# Parasite.net
KiCad netlist of a schematic drawn in Altium Designer
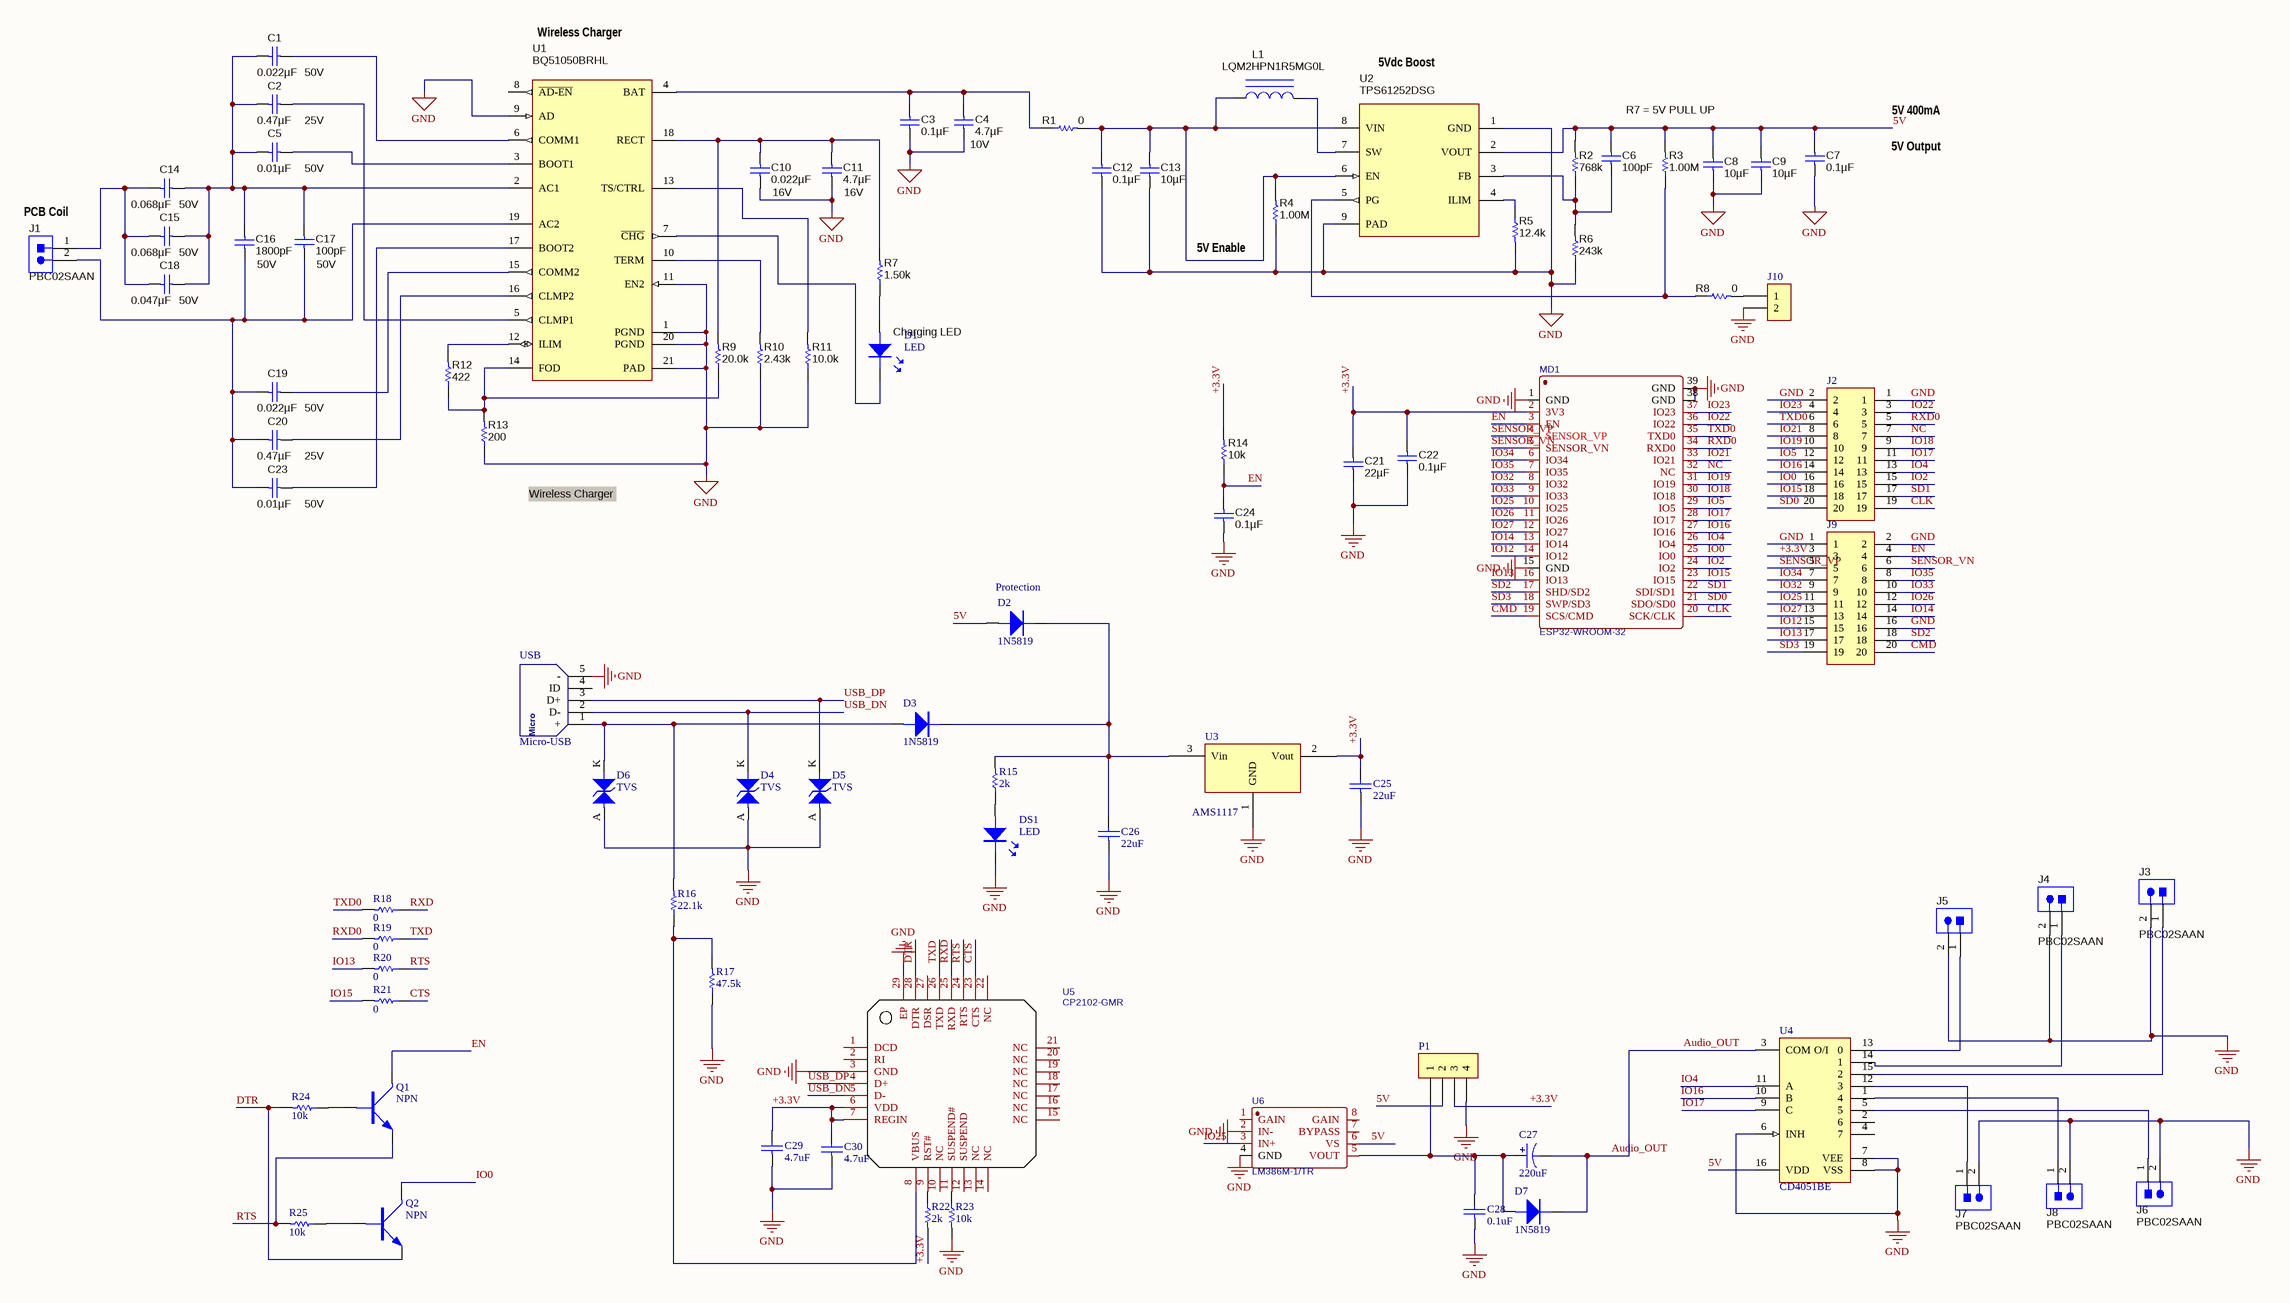
[diagram p0: Parasite.SchDoc]

(export (version "E")
  (design (tool "Eeschema 10.0.6"))
  (components
    (comp (ref "C1")
      (value "GRM155R71H223KA12D")
      (footprint "0603C")
      (description "CAP, CERM, 0.022 µF, 50 V, +/- 10%, X7R, 0402")
      (fields
        (field (name "VALUEDISPLAYED") "0.022µF")
        (field (name "MANUFACTURER") "MuRata")
        (field (name "VALUE2") "50V")
        (field (name "PUBLISHER") "Texas Instruments")
      )
      (libsource (lib "magsound") (part "GRM155R71H223KA12D"))
    )
    (comp (ref "C2")
      (value "~")
      (footprint "0603C")
      (description "CAP, CERM, 0.47 µF, 25 V, +/- 10%, X7R, 0603")
      (fields
        (field (name "PARTNUMBER") "GRM188R71E474KA12D")
        (field (name "VALUEDISPLAYED") "0.47µF")
        (field (name "MANUFACTURER") "MuRata")
        (field (name "VALUE2") "25V")
        (field (name "PUBLISHER") "Texas Instruments")
      )
      (libsource (lib "magsound") (part "GRM188R71E474KA12D"))
    )
    (comp (ref "C3")
      (value "GRM155R71A104KA01D")
      (footprint "0603C")
      (description "CAP, CERM, 0.1 µF, 10 V, +/- 10%, X7R, 0402")
      (fields
        (field (name "VALUEDISPLAYED") "0.1µF")
        (field (name "MANUFACTURER") "MuRata")
        (field (name "PUBLISHER") "Texas Instruments")
      )
      (libsource (lib "Capacitor_Ceramic") (part "GRM155R71A104KA01D"))
    )
    (comp (ref "C4")
      (value "C1005X5R1A475K050BC")
      (footprint "0603C")
      (description "CAP, CERM, 4.7 µF, 10 V, +/- 10%, X5R, 0402")
      (fields
        (field (name "VALUEDISPLAYED") "4.7µF")
        (field (name "MANUFACTURER") "TDK")
        (field (name "VALUE2") "10V")
        (field (name "PUBLISHER") "Texas Instruments")
      )
      (libsource (lib "Capacitor_Ceramic") (part "C1005X5R1A475K050BC"))
    )
    (comp (ref "C5")
      (value "~")
      (footprint "0603C")
      (description "CAP, CERM, 0.01 µF, 50 V, +/- 5%, X7R, 0402")
      (fields
        (field (name "PARTNUMBER") "C0402C103J5RACTU")
        (field (name "VALUEDISPLAYED") "0.01µF")
        (field (name "MANUFACTURER") "Kemet")
        (field (name "VALUE2") "50V")
        (field (name "PUBLISHER") "Texas Instruments")
      )
      (libsource (lib "magsound") (part "C0402C103J5RACTU"))
    )
    (comp (ref "C6")
      (value "CC0402JRNPO9BN101")
      (footprint "0603C")
      (description "CAP, CERM, 100 pF, 50 V, +/- 5%, C0G/NP0, 0402")
      (fields
        (field (name "VALUEDISPLAYED") "100pF")
        (field (name "MANUFACTURER") "Yageo America")
        (field (name "PUBLISHER") "Texas Instruments")
      )
      (libsource (lib "Capacitor_Ceramic") (part "CC0402JRNPO9BN101"))
    )
    (comp (ref "C7")
      (value "GRM155R71A104KA01D")
      (footprint "0603C")
      (description "CAP, CERM, 0.1 µF, 10 V, +/- 10%, X7R, 0402")
      (fields
        (field (name "VALUEDISPLAYED") "0.1µF")
        (field (name "MANUFACTURER") "MuRata")
        (field (name "PUBLISHER") "Texas Instruments")
      )
      (libsource (lib "Capacitor_Ceramic") (part "GRM155R71A104KA01D"))
    )
    (comp (ref "C8")
      (value "C0603C106M9PACTU")
      (footprint "0603C")
      (description "CAP, CERM, 10 µF, 6.3 V, +/- 20%, X5R, 0603")
      (fields
        (field (name "VALUEDISPLAYED") "10µF")
        (field (name "MANUFACTURER") "Kemet")
        (field (name "PUBLISHER") "Texas Instruments")
      )
      (libsource (lib "Capacitor_Ceramic") (part "C0603C106M9PACTU"))
    )
    (comp (ref "C9")
      (value "C0603C106M9PACTU")
      (footprint "0603C")
      (description "CAP, CERM, 10 µF, 6.3 V, +/- 20%, X5R, 0603")
      (fields
        (field (name "VALUEDISPLAYED") "10µF")
        (field (name "MANUFACTURER") "Kemet")
        (field (name "PUBLISHER") "Texas Instruments")
      )
      (libsource (lib "Capacitor_Ceramic") (part "C0603C106M9PACTU"))
    )
    (comp (ref "C10")
      (value "C1005X7R1C223K")
      (footprint "0603C")
      (description "CAP, CERM, 0.022 µF, 16 V, +/- 10%, X7R, 0402")
      (fields
        (field (name "VALUEDISPLAYED") "0.022µF")
        (field (name "MANUFACTURER") "TDK")
        (field (name "VALUE2") "16V")
        (field (name "PUBLISHER") "Texas Instruments")
      )
      (libsource (lib "Capacitor_Ceramic") (part "C1005X7R1C223K"))
    )
    (comp (ref "C11")
      (value "GRM188R61C475KAAJ")
      (footprint "0603C")
      (description "CAP, CERM, 4.7 µF, 16 V, +/- 10%, X5R, 0603")
      (fields
        (field (name "VALUEDISPLAYED") "4.7µF")
        (field (name "MANUFACTURER") "MuRata")
        (field (name "VALUE2") "16V")
        (field (name "PUBLISHER") "Texas Instruments")
      )
      (libsource (lib "Capacitor_Ceramic") (part "GRM188R61C475KAAJ"))
    )
    (comp (ref "C12")
      (value "GRM155R71A104KA01D")
      (footprint "0603C")
      (description "CAP, CERM, 0.1 µF, 10 V, +/- 10%, X7R, 0402")
      (fields
        (field (name "VALUEDISPLAYED") "0.1µF")
        (field (name "MANUFACTURER") "MuRata")
        (field (name "PUBLISHER") "Texas Instruments")
      )
      (libsource (lib "Capacitor_Ceramic") (part "GRM155R71A104KA01D"))
    )
    (comp (ref "C13")
      (value "C0603C106M9PACTU")
      (footprint "0603C")
      (description "CAP, CERM, 10 µF, 6.3 V, +/- 20%, X5R, 0603")
      (fields
        (field (name "VALUEDISPLAYED") "10µF")
        (field (name "MANUFACTURER") "Kemet")
        (field (name "PUBLISHER") "Texas Instruments")
      )
      (libsource (lib "Capacitor_Ceramic") (part "C0603C106M9PACTU"))
    )
    (comp (ref "C14")
      (value "C1005X7R1H683K")
      (footprint "0603C")
      (description "CAP, CERM, 0.068 µF, 50 V, +/- 10%, X7R, 0402")
      (fields
        (field (name "VALUEDISPLAYED") "0.068µF")
        (field (name "MANUFACTURER") "TDK")
        (field (name "VALUE2") "50V")
        (field (name "PUBLISHER") "Texas Instruments")
      )
      (libsource (lib "Capacitor_Ceramic") (part "C1005X7R1H683K"))
    )
    (comp (ref "C15")
      (value "C1005X7R1H683K")
      (footprint "0603C")
      (description "CAP, CERM, 0.068 µF, 50 V, +/- 10%, X7R, 0402")
      (fields
        (field (name "VALUEDISPLAYED") "0.068µF")
        (field (name "MANUFACTURER") "TDK")
        (field (name "VALUE2") "50V")
        (field (name "PUBLISHER") "Texas Instruments")
      )
      (libsource (lib "Capacitor_Ceramic") (part "C1005X7R1H683K"))
    )
    (comp (ref "C16")
      (value "GRM1885C1H182JA01D")
      (footprint "0603C")
      (description "CAP, CERM, 1800 pF, 50 V, +/- 5%, C0G/NP0, 0603")
      (fields
        (field (name "VALUEDISPLAYED") "1800pF")
        (field (name "MANUFACTURER") "MuRata")
        (field (name "VALUE2") "50V")
        (field (name "PUBLISHER") "Texas Instruments")
      )
      (libsource (lib "Capacitor_Ceramic") (part "GRM1885C1H182JA01D"))
    )
    (comp (ref "C17")
      (value "CC0402JRNPO9BN101")
      (footprint "0603C")
      (description "CAP, CERM, 100 pF, 50 V, +/- 5%, C0G/NP0, 0402")
      (fields
        (field (name "VALUEDISPLAYED") "100pF")
        (field (name "MANUFACTURER") "Yageo America")
        (field (name "VALUE2") "50V")
        (field (name "PUBLISHER") "Texas Instruments")
      )
      (libsource (lib "Capacitor_Ceramic") (part "CC0402JRNPO9BN101"))
    )
    (comp (ref "C18")
      (value "GRM188R71H473KA61D")
      (footprint "0603C")
      (description "CAP, CERM, 0.047 µF, 50 V, +/- 10%, X7R, 0603")
      (fields
        (field (name "VALUEDISPLAYED") "0.047µF")
        (field (name "MANUFACTURER") "MuRata")
        (field (name "VALUE2") "50V")
        (field (name "PUBLISHER") "Texas Instruments")
      )
      (libsource (lib "Capacitor_Ceramic") (part "GRM188R71H473KA61D"))
    )
    (comp (ref "C19")
      (value "GRM155R71H223KA12D")
      (footprint "0603C")
      (description "CAP, CERM, 0.022 µF, 50 V, +/- 10%, X7R, 0402")
      (fields
        (field (name "VALUEDISPLAYED") "0.022µF")
        (field (name "MANUFACTURER") "MuRata")
        (field (name "VALUE2") "50V")
        (field (name "PUBLISHER") "Texas Instruments")
      )
      (libsource (lib "Capacitor_Ceramic") (part "GRM155R71H223KA12D"))
    )
    (comp (ref "C20")
      (value "GRM188R71E474KA12D")
      (footprint "0603C")
      (description "CAP, CERM, 0.47 µF, 25 V, +/- 10%, X7R, 0603")
      (fields
        (field (name "VALUEDISPLAYED") "0.47µF")
        (field (name "MANUFACTURER") "MuRata")
        (field (name "VALUE2") "25V")
        (field (name "PUBLISHER") "Texas Instruments")
      )
      (libsource (lib "Capacitor_Ceramic") (part "GRM188R71E474KA12D"))
    )
    (comp (ref "C21")
      (value "GRM155R71A104KA01D")
      (footprint "0603C")
      (description "CAP, CERM, 0.1 µF, 10 V, +/- 10%, X7R, 0402")
      (fields
        (field (name "VALUEDISPLAYED") "22µF")
        (field (name "MANUFACTURER") "MuRata")
        (field (name "PUBLISHER") "Texas Instruments")
      )
      (libsource (lib "Capacitor_Ceramic") (part "GRM155R71A104KA01D"))
    )
    (comp (ref "C22")
      (value "GRM155R71A104KA01D")
      (footprint "0603C")
      (description "CAP, CERM, 0.1 µF, 10 V, +/- 10%, X7R, 0402")
      (fields
        (field (name "VALUEDISPLAYED") "0.1µF")
        (field (name "MANUFACTURER") "MuRata")
        (field (name "PUBLISHER") "Texas Instruments")
      )
      (libsource (lib "Capacitor_Ceramic") (part "GRM155R71A104KA01D"))
    )
    (comp (ref "C23")
      (value "C0402C103J5RACTU")
      (footprint "0603C")
      (description "CAP, CERM, 0.01 µF, 50 V, +/- 5%, X7R, 0402")
      (fields
        (field (name "VALUEDISPLAYED") "0.01µF")
        (field (name "MANUFACTURER") "Kemet")
        (field (name "VALUE2") "50V")
        (field (name "PUBLISHER") "Texas Instruments")
      )
      (libsource (lib "Capacitor_Ceramic") (part "C0402C103J5RACTU"))
    )
    (comp (ref "C24")
      (value "GRM155R71A104KA01D")
      (footprint "0603C")
      (description "CAP, CERM, 0.1 µF, 10 V, +/- 10%, X7R, 0402")
      (fields
        (field (name "VALUEDISPLAYED") "0.1µF")
        (field (name "MANUFACTURER") "MuRata")
        (field (name "PUBLISHER") "Texas Instruments")
      )
      (libsource (lib "Capacitor_Ceramic") (part "GRM155R71A104KA01D"))
    )
    (comp (ref "C25")
      (value "22uF")
      (footprint "0603C")
      (description "无极性电容")
      (libsource (lib "电容") (part "CAP"))
    )
    (comp (ref "C26")
      (value "22uF")
      (footprint "0603C")
      (description "无极性电容")
      (libsource (lib "电容") (part "CAP"))
    )
    (comp (ref "C27")
      (value "220uF")
      (footprint "TAJ-B/3528")
      (description "钽电容")
      (libsource (lib "电容") (part "TCAP"))
    )
    (comp (ref "C28")
      (value "0.1uF")
      (footprint "0603C")
      (description "无极性电容")
      (libsource (lib "电容") (part "CAP"))
    )
    (comp (ref "C29")
      (value "4.7uF")
      (footprint "0603C")
      (description "无极性电容")
      (libsource (lib "电容") (part "CAP"))
    )
    (comp (ref "C30")
      (value "4.7uF")
      (footprint "0603C")
      (description "无极性电容")
      (libsource (lib "电容") (part "CAP"))
    )
    (comp (ref "D1") (value "LED") (footprint "LED-0603G") (libsource (lib "LED") (part "LED")))
    (comp (ref "D2")
      (value "1N5819")
      (footprint "SOD-123")
      (description "普通二极管")
      (libsource (lib "二极管") (part "DIODE"))
    )
    (comp (ref "D3")
      (value "1N5819")
      (footprint "SOD-123")
      (description "普通二极管")
      (libsource (lib "二极管") (part "DIODE"))
    )
    (comp (ref "D4")
      (value "TVS")
      (footprint "SOD-523")
      (description "双向瞬态抑制二极管")
      (libsource (lib "二极管") (part "TVS"))
    )
    (comp (ref "D5")
      (value "TVS")
      (footprint "SOD-523")
      (description "双向瞬态抑制二极管")
      (libsource (lib "二极管") (part "TVS"))
    )
    (comp (ref "D6")
      (value "TVS")
      (footprint "SOD-523")
      (description "双向瞬态抑制二极管")
      (libsource (lib "二极管") (part "TVS"))
    )
    (comp (ref "D7")
      (value "1N5819")
      (footprint "SOD-123")
      (description "普通二极管")
      (libsource (lib "二极管") (part "DIODE"))
    )
    (comp (ref "DS1") (value "LED") (footprint "LED-0603B") (libsource (lib "LED") (part "LED")))
    (comp (ref "J1")
      (value "PBC02SAAN")
      (footprint "Pin HDR1X2/2.54mm-S")
      (description "Header, 100mil, 2x1, Gold, TH")
      (fields
        (field (name "MANUFACTURER") "Sullins Connector Solutions")
        (field (name "SYMBOLCREATOR") "a0412235")
        (field (name "PUBLISHER") "Texas Instruments")
      )
      (libsource (lib "") (part "PBC02SAAN_2"))
    )
    (comp (ref "J2")
      (value "~")
      (footprint "Pin HDR2X10/2.54mm-S")
      (libsource (lib "排针") (part "Pin HDR2X10"))
    )
    (comp (ref "J3")
      (value "PBC02SAAN")
      (footprint "Pin HDR1X2/2.54mm-S")
      (description "Header, 100mil, 2x1, Gold, TH")
      (fields
        (field (name "MANUFACTURER") "Sullins Connector Solutions")
        (field (name "SYMBOLCREATOR") "a0412235")
        (field (name "PUBLISHER") "Texas Instruments")
      )
      (libsource (lib "") (part "PBC02SAAN_1"))
    )
    (comp (ref "J4")
      (value "PBC02SAAN")
      (footprint "Pin HDR1X2/2.54mm-S")
      (description "Header, 100mil, 2x1, Gold, TH")
      (fields
        (field (name "MANUFACTURER") "Sullins Connector Solutions")
        (field (name "SYMBOLCREATOR") "a0412235")
        (field (name "PUBLISHER") "Texas Instruments")
      )
      (libsource (lib "magsound") (part "PBC02SAAN"))
    )
    (comp (ref "J5")
      (value "~")
      (footprint "Pin HDR1X2/2.54mm-S")
      (description "Header, 100mil, 2x1, Gold, TH")
      (fields
        (field (name "PARTNUMBER") "PBC02SAAN")
        (field (name "MANUFACTURER") "Sullins Connector Solutions")
        (field (name "SYMBOLCREATOR") "a0412235")
        (field (name "PUBLISHER") "Texas Instruments")
      )
      (libsource (lib "magsound") (part "PBC02SAAN"))
    )
    (comp (ref "J6")
      (value "PBC02SAAN")
      (footprint "Pin HDR1X2/2.54mm-S")
      (description "Header, 100mil, 2x1, Gold, TH")
      (fields
        (field (name "MANUFACTURER") "Sullins Connector Solutions")
        (field (name "SYMBOLCREATOR") "a0412235")
        (field (name "PUBLISHER") "Texas Instruments")
      )
      (libsource (lib "Connectors_Sullins") (part "PBC02SAAN"))
    )
    (comp (ref "J7")
      (value "PBC02SAAN")
      (footprint "Pin HDR1X2/2.54mm-S")
      (description "Header, 100mil, 2x1, Gold, TH")
      (fields
        (field (name "MANUFACTURER") "Sullins Connector Solutions")
        (field (name "SYMBOLCREATOR") "a0412235")
        (field (name "PUBLISHER") "Texas Instruments")
      )
      (libsource (lib "Connectors_Sullins") (part "PBC02SAAN"))
    )
    (comp (ref "J8")
      (value "PBC02SAAN")
      (footprint "Pin HDR1X2/2.54mm-S")
      (description "Header, 100mil, 2x1, Gold, TH")
      (fields
        (field (name "MANUFACTURER") "Sullins Connector Solutions")
        (field (name "SYMBOLCREATOR") "a0412235")
        (field (name "PUBLISHER") "Texas Instruments")
      )
      (libsource (lib "Connectors_Sullins") (part "PBC02SAAN"))
    )
    (comp (ref "J9")
      (value "~")
      (footprint "Pin HDR2X10/2.54mm-S")
      (libsource (lib "") (part "Pin HDR2X10_1"))
    )
    (comp (ref "J10")
      (value "~")
      (footprint "Pin HDR1X2/2.54mm-S")
      (libsource (lib "排针") (part "Pin HDR1X2"))
    )
    (comp (ref "L1")
      (value "LQM2HPN1R5MG0L")
      (footprint "L1008")
      (description "Inductor, Multilayer, Ferrite, 1.5 µH, 1.5 A, 0.07 ohm, SMD")
      (fields (field (name "MANUFACTURER") "MuRata") (field (name "PUBLISHER") "Texas Instruments"))
      (libsource (lib "Inductor_MuRata") (part "LQM2HPN1R5MG0L"))
    )
    (comp (ref "MD1")
      (value "ESP32-WROOM-32")
      (footprint "WIFIM-SMD_ESP-32S")
      (fields (field (name "BOM_SUPPLIER PART") "C82899") (field (name "CONTRIBUTOR") "LCSC"))
      (libsource (lib "ESP32-WROOM-32_2022-07-12") (part "ESP32-WROOM-32"))
    )
    (comp (ref "P1") (value "~") (footprint "Pin HDR1X4/2.54mm-S") (libsource (lib "排针") (part "Pin HDR1X4")))
    (comp (ref "Q1")
      (value "NPN")
      (footprint "SOT-23")
      (description "NPN三极管")
      (libsource (lib "三极管") (part "NPN"))
    )
    (comp (ref "Q2")
      (value "NPN")
      (footprint "SOT-23")
      (description "NPN三极管")
      (libsource (lib "三极管") (part "NPN"))
    )
    (comp (ref "R1")
      (value "CRCW04020000Z0ED")
      (footprint "0603R")
      (description "RES, 0, 5%, 0.063 W, 0402")
      (fields
        (field (name "VALUEDISPLAYED") "0")
        (field (name "MANUFACTURER") "Vishay-Dale")
        (field (name "PUBLISHER") "Texas Instruments")
      )
      (libsource (lib "Resistor_0402") (part "CRCW04020000Z0ED"))
    )
    (comp (ref "R2")
      (value "CRCW0402768KFKED")
      (footprint "0603R")
      (description "RES, 768 k, 1%, 0.063 W, 0402")
      (fields
        (field (name "VALUEDISPLAYED") "768k")
        (field (name "MANUFACTURER") "Vishay-Dale")
        (field (name "PUBLISHER") "Texas Instruments")
      )
      (libsource (lib "Resistor_0402") (part "CRCW0402768KFKED"))
    )
    (comp (ref "R3")
      (value "CRCW04021M00FKED")
      (footprint "0603R")
      (description "RES, 1.00 M, 1%, 0.063 W, 0402")
      (fields
        (field (name "VALUEDISPLAYED") "1.00M")
        (field (name "MANUFACTURER") "Vishay-Dale")
        (field (name "PUBLISHER") "Texas Instruments")
      )
      (libsource (lib "Resistor_0402") (part "CRCW04021M00FKED"))
    )
    (comp (ref "R4")
      (value "CRCW04021M00FKED")
      (footprint "0603R")
      (description "RES, 1.00 M, 1%, 0.063 W, 0402")
      (fields
        (field (name "VALUEDISPLAYED") "1.00M")
        (field (name "MANUFACTURER") "Vishay-Dale")
        (field (name "PUBLISHER") "Texas Instruments")
      )
      (libsource (lib "Resistor_0402") (part "CRCW04021M00FKED"))
    )
    (comp (ref "R5")
      (value "CRCW040212K4FKED")
      (footprint "0603R")
      (description "RES, 12.4 k, 1%, 0.063 W, 0402")
      (fields
        (field (name "VALUEDISPLAYED") "12.4k")
        (field (name "MANUFACTURER") "Vishay-Dale")
        (field (name "PUBLISHER") "Texas Instruments")
      )
      (libsource (lib "Resistor_0402") (part "CRCW040212K4FKED"))
    )
    (comp (ref "R6")
      (value "CRCW0402243KFKED")
      (footprint "0603R")
      (description "RES, 243 k, 1%, 0.063 W, 0402")
      (fields
        (field (name "VALUEDISPLAYED") "243k")
        (field (name "MANUFACTURER") "Vishay-Dale")
        (field (name "PUBLISHER") "Texas Instruments")
      )
      (libsource (lib "Resistor_0402") (part "CRCW0402243KFKED"))
    )
    (comp (ref "R7")
      (value "CRCW04021K50FKED")
      (footprint "0603R")
      (description "RES, 1.50 k, 1%, 0.063 W, 0402")
      (fields
        (field (name "VALUEDISPLAYED") "1.50k")
        (field (name "MANUFACTURER") "Vishay-Dale")
        (field (name "PUBLISHER") "Texas Instruments")
      )
      (libsource (lib "Resistor_0402") (part "CRCW04021K50FKED"))
    )
    (comp (ref "R8")
      (value "CRCW04020000Z0ED")
      (footprint "0603R")
      (description "RES, 0, 5%, 0.063 W, 0402")
      (fields
        (field (name "VALUEDISPLAYED") "0")
        (field (name "MANUFACTURER") "Vishay-Dale")
        (field (name "PUBLISHER") "Texas Instruments")
      )
      (libsource (lib "Resistor_0402") (part "CRCW04020000Z0ED"))
    )
    (comp (ref "R9")
      (value "CRCW040220K0FKED")
      (footprint "0603R")
      (description "RES, 20.0 k, 1%, 0.063 W, 0402")
      (fields
        (field (name "VALUEDISPLAYED") "20.0k")
        (field (name "MANUFACTURER") "Vishay-Dale")
        (field (name "PUBLISHER") "Texas Instruments")
      )
      (libsource (lib "Resistor_0402") (part "CRCW040220K0FKED"))
    )
    (comp (ref "R10")
      (value "CRCW04022K43FKED")
      (footprint "0603R")
      (description "RES, 2.43 k, 1%, 0.063 W, 0402")
      (fields
        (field (name "VALUEDISPLAYED") "2.43k")
        (field (name "MANUFACTURER") "Vishay-Dale")
        (field (name "PUBLISHER") "Texas Instruments")
      )
      (libsource (lib "Resistor_0402") (part "CRCW04022K43FKED"))
    )
    (comp (ref "R11")
      (value "CRCW040210K0FKED")
      (footprint "0603R")
      (description "RES, 10.0 k, 1%, 0.063 W, 0402")
      (fields
        (field (name "VALUEDISPLAYED") "10.0k")
        (field (name "MANUFACTURER") "Vishay-Dale")
        (field (name "PUBLISHER") "Texas Instruments")
      )
      (libsource (lib "Resistor_0402") (part "CRCW040210K0FKED"))
    )
    (comp (ref "R12")
      (value "~")
      (footprint "0603R")
      (description "RES, 422, 1%, 0.063 W, 0402")
      (fields
        (field (name "PARTNUMBER") "CRCW0402422RFKED")
        (field (name "VALUEDISPLAYED") "422")
        (field (name "MANUFACTURER") "Vishay-Dale")
        (field (name "PUBLISHER") "Texas Instruments")
      )
      (libsource (lib "magsound") (part "CRCW0402422RFKED"))
    )
    (comp (ref "R13")
      (value "~")
      (footprint "0603R")
      (description "RES, 200, 1%, 0.063 W, 0402")
      (fields
        (field (name "PARTNUMBER") "CRCW0402200RFKED")
        (field (name "VALUEDISPLAYED") "200")
        (field (name "MANUFACTURER") "Vishay-Dale")
        (field (name "PUBLISHER") "Texas Instruments")
      )
      (libsource (lib "magsound") (part "CRCW0402200RFKED"))
    )
    (comp (ref "R14")
      (value "10k")
      (footprint "0603R")
      (description "RES, 1.00 M, 1%, 0.063 W, 0402")
      (fields
        (field (name "PARTNUMBER") "CRCW04021M00FKED")
        (field (name "VALUEDISPLAYED") "10k")
        (field (name "MANUFACTURER") "Vishay-Dale")
        (field (name "PUBLISHER") "Texas Instruments")
      )
      (libsource (lib "Resistor_0402") (part "CRCW04021M00FKED"))
    )
    (comp (ref "R15") (value "2k") (footprint "0603R") (libsource (lib "电阻") (part "RES")))
    (comp (ref "R16") (value "22.1k") (footprint "0603R") (libsource (lib "电阻") (part "RES")))
    (comp (ref "R17") (value "47.5k") (footprint "0603R") (libsource (lib "电阻") (part "RES")))
    (comp (ref "R18") (value "0") (footprint "0603R") (libsource (lib "电阻") (part "RES")))
    (comp (ref "R19") (value "0") (footprint "0603R") (libsource (lib "电阻") (part "RES")))
    (comp (ref "R20") (value "0") (footprint "0603R") (libsource (lib "电阻") (part "RES")))
    (comp (ref "R21") (value "0") (footprint "0603R") (libsource (lib "电阻") (part "RES")))
    (comp (ref "R22") (value "2k") (footprint "0603R") (libsource (lib "电阻") (part "RES")))
    (comp (ref "R23") (value "10k") (footprint "0603R") (libsource (lib "电阻") (part "RES")))
    (comp (ref "R24") (value "10k") (footprint "0603R") (libsource (lib "电阻") (part "RES")))
    (comp (ref "R25") (value "10k") (footprint "0603R") (libsource (lib "电阻") (part "RES")))
    (comp (ref "U1")
      (value "BQ51050BRHL")
      (footprint "QFN-20_L4.7-W3.7-P0.50-BL-EP")
      (description "High-Efficiency Qi v1.1-Compliant Wireless Power Receiver and Battery Charger, RHL0020A")
      (fields
        (field (name "MANUFACTURER") "Texas Instruments")
        (field (name "SYMBOLCREATOR") "a0411947")
        (field (name "PUBLISHER") "Texas Instruments")
      )
      (libsource (lib "TI_Pre_Release") (part "BQ51050BRHL"))
    )
    (comp (ref "U2")
      (value "TPS61252DSG")
      (footprint "WSON-8_L2.0-W2.0-P0.65-BL-EP")
      (description "TINY 1.5-A BOOST CONVERTER WITH ADJUSTABLE INPUT CURRENT LIMIT, DSG0008A")
      (fields
        (field (name "MANUFACTURER") "Texas Instruments")
        (field (name "SYMBOLCREATOR") "a0799628")
        (field (name "PUBLISHER") "Texas Instruments")
      )
      (libsource (lib "TI_Pre_Release") (part "TPS61252DSG"))
    )
    (comp (ref "U3")
      (value "AMS1117")
      (footprint "SOT223")
      (description "三端稳压芯片")
      (libsource (lib "电源芯片") (part "AMS1117"))
    )
    (comp (ref "U4")
      (value "CD4051BE")
      (footprint "DIP16")
      (description "CMOS Single 8-Channel Analog Multiplexer/Demultiplexer with Logic-Level Conversion, N0016A, TUBE")
      (fields
        (field (name "GENERIC PART NUMBER") "CD4051B")
        (field (name "MANUFACTURER") "Texas Instruments")
      )
      (libsource (lib "保险丝") (part "TI-CD4051B-16"))
    )
    (comp (ref "U5")
      (value "CP2102-GMR")
      (footprint "WQFN-28_L5.0-W5.0-P0.50-BL-EP3.2")
      (fields (field (name "BOM_SUPPLIER PART") "C6568"))
      (libsource (lib "CP2102-GMR_2022-07-11") (part "CP2102-GMR"))
    )
    (comp (ref "U6")
      (value "LM386M-1/TR")
      (footprint "SOP-8_L5.0-W4.0-P1.27-LS6.0-BL")
      (fields (field (name "BOM_SUPPLIER PART") "C383071") (field (name "CONTRIBUTOR") "LCSC"))
      (libsource (lib "LM386M-1TR_2022-07-11") (part "LM386M-1/TR"))
    )
    (comp (ref "USB")
      (value "Micro-USB")
      (footprint "USB-micro_B")
      (libsource (lib "USB") (part "Micro-USB"))
    )
  )
  (nets
    (net (code "1") (name "/+3.3V") (class "Default")
      (node (ref "C21") (pin "1") (pinfunction "1_1") (pintype "passive"))
      (node (ref "C22") (pin "1") (pinfunction "1_1") (pintype "passive"))
      (node (ref "C25") (pin "2") (pinfunction "2_2") (pintype "passive"))
      (node (ref "C29") (pin "2") (pinfunction "2_2") (pintype "passive"))
      (node (ref "C30") (pin "2") (pinfunction "2_2") (pintype "passive"))
      (node (ref "J9") (pin "3") (pinfunction "3_3") (pintype "passive"))
      (node (ref "MD1") (pin "2") (pinfunction "3V3_2") (pintype "passive"))
      (node (ref "P1") (pin "3") (pinfunction "3_3") (pintype "passive"))
      (node (ref "R14") (pin "2") (pinfunction "2_2") (pintype "passive"))
      (node (ref "R22") (pin "2") (pinfunction "2_2") (pintype "passive"))
      (node (ref "U3") (pin "2") (pinfunction "Vout_2") (pintype "passive"))
      (node (ref "U5") (pin "6") (pinfunction "VDD_6") (pintype "passive"))
      (node (ref "U5") (pin "7") (pinfunction "REGIN_7") (pintype "passive"))
    )
    (net (code "2") (name "/5V") (class "Default")
      (node (ref "C6") (pin "1") (pinfunction "1_1") (pintype "passive"))
      (node (ref "C7") (pin "1") (pinfunction "1_1") (pintype "passive"))
      (node (ref "C8") (pin "1") (pinfunction "1_1") (pintype "passive"))
      (node (ref "C9") (pin "1") (pinfunction "1_1") (pintype "passive"))
      (node (ref "D2") (pin "A") (pinfunction "A_A") (pintype "passive"))
      (node (ref "P1") (pin "2") (pinfunction "2_2") (pintype "passive"))
      (node (ref "R2") (pin "2") (pinfunction "2_2") (pintype "passive"))
      (node (ref "R3") (pin "2") (pinfunction "2_2") (pintype "passive"))
      (node (ref "U2") (pin "2") (pinfunction "VOUT_2") (pintype "power_in"))
      (node (ref "U4") (pin "16") (pinfunction "VDD_16") (pintype "power_in"))
      (node (ref "U6") (pin "6") (pinfunction "VS_6") (pintype "passive"))
    )
    (net (code "3") (name "/Audio_OUT") (class "Default")
      (node (ref "C27") (pin "2") (pinfunction "2_2") (pintype "passive"))
      (node (ref "D7") (pin "K") (pinfunction "K_K") (pintype "passive"))
      (node (ref "U4") (pin "3") (pinfunction "COM_O/I_3") (pintype "passive"))
    )
    (net (code "4") (name "/CLK") (class "Default")
      (node (ref "J2") (pin "19") (pinfunction "19_19") (pintype "passive"))
      (node (ref "MD1") (pin "20") (pinfunction "SCK/CLK_20") (pintype "passive"))
    )
    (net (code "5") (name "/CMD") (class "Default")
      (node (ref "J9") (pin "20") (pinfunction "20_20") (pintype "passive"))
      (node (ref "MD1") (pin "19") (pinfunction "SCS/CMD_19") (pintype "passive"))
    )
    (net (code "6") (name "/CTS") (class "Default")
      (node (ref "R21") (pin "1") (pinfunction "1_1") (pintype "passive"))
      (node (ref "U5") (pin "23") (pinfunction "CTS_23") (pintype "passive"))
    )
    (net (code "7") (name "/DTR") (class "Default")
      (node (ref "Q2") (pin "E") (pinfunction "E_E") (pintype "passive"))
      (node (ref "R24") (pin "2") (pinfunction "2_2") (pintype "passive"))
      (node (ref "U5") (pin "28") (pinfunction "DTR_28") (pintype "passive"))
    )
    (net (code "8") (name "/EN") (class "Default")
      (node (ref "C24") (pin "1") (pinfunction "1_1") (pintype "passive"))
      (node (ref "J9") (pin "4") (pinfunction "4_4") (pintype "passive"))
      (node (ref "MD1") (pin "3") (pinfunction "EN_3") (pintype "passive"))
      (node (ref "Q1") (pin "C") (pinfunction "C_C") (pintype "passive"))
      (node (ref "R14") (pin "1") (pinfunction "1_1") (pintype "passive"))
    )
    (net (code "9") (name "/IO0") (class "Default")
      (node (ref "J2") (pin "16") (pinfunction "16_16") (pintype "passive"))
      (node (ref "MD1") (pin "25") (pinfunction "IO0_25") (pintype "passive"))
      (node (ref "Q2") (pin "C") (pinfunction "C_C") (pintype "passive"))
    )
    (net (code "10") (name "/IO2") (class "Default")
      (node (ref "J2") (pin "15") (pinfunction "15_15") (pintype "passive"))
      (node (ref "MD1") (pin "24") (pinfunction "IO2_24") (pintype "passive"))
    )
    (net (code "11") (name "/IO4") (class "Default")
      (node (ref "J2") (pin "13") (pinfunction "13_13") (pintype "passive"))
      (node (ref "MD1") (pin "26") (pinfunction "IO4_26") (pintype "passive"))
      (node (ref "U4") (pin "11") (pinfunction "A_11") (pintype "passive"))
    )
    (net (code "12") (name "/IO5") (class "Default")
      (node (ref "J2") (pin "12") (pinfunction "12_12") (pintype "passive"))
      (node (ref "MD1") (pin "29") (pinfunction "IO5_29") (pintype "passive"))
    )
    (net (code "13") (name "/IO12") (class "Default")
      (node (ref "J9") (pin "15") (pinfunction "15_15") (pintype "passive"))
      (node (ref "MD1") (pin "14") (pinfunction "IO12_14") (pintype "passive"))
    )
    (net (code "14") (name "/IO13") (class "Default")
      (node (ref "J9") (pin "17") (pinfunction "17_17") (pintype "passive"))
      (node (ref "MD1") (pin "16") (pinfunction "IO13_16") (pintype "passive"))
      (node (ref "R20") (pin "2") (pinfunction "2_2") (pintype "passive"))
    )
    (net (code "15") (name "/IO14") (class "Default")
      (node (ref "J9") (pin "14") (pinfunction "14_14") (pintype "passive"))
      (node (ref "MD1") (pin "13") (pinfunction "IO14_13") (pintype "passive"))
    )
    (net (code "16") (name "/IO15") (class "Default")
      (node (ref "J2") (pin "18") (pinfunction "18_18") (pintype "passive"))
      (node (ref "MD1") (pin "23") (pinfunction "IO15_23") (pintype "passive"))
      (node (ref "R21") (pin "2") (pinfunction "2_2") (pintype "passive"))
    )
    (net (code "17") (name "/IO16") (class "Default")
      (node (ref "J2") (pin "14") (pinfunction "14_14") (pintype "passive"))
      (node (ref "MD1") (pin "27") (pinfunction "IO16_27") (pintype "passive"))
      (node (ref "U4") (pin "10") (pinfunction "B_10") (pintype "passive"))
    )
    (net (code "18") (name "/IO17") (class "Default")
      (node (ref "J2") (pin "11") (pinfunction "11_11") (pintype "passive"))
      (node (ref "MD1") (pin "28") (pinfunction "IO17_28") (pintype "passive"))
      (node (ref "U4") (pin "9") (pinfunction "C_9") (pintype "passive"))
    )
    (net (code "19") (name "/IO18") (class "Default")
      (node (ref "J2") (pin "9") (pinfunction "9_9") (pintype "passive"))
      (node (ref "MD1") (pin "30") (pinfunction "IO18_30") (pintype "passive"))
    )
    (net (code "20") (name "/IO19") (class "Default")
      (node (ref "J2") (pin "10") (pinfunction "10_10") (pintype "passive"))
      (node (ref "MD1") (pin "31") (pinfunction "IO19_31") (pintype "passive"))
    )
    (net (code "21") (name "/IO21") (class "Default")
      (node (ref "J2") (pin "8") (pinfunction "8_8") (pintype "passive"))
      (node (ref "MD1") (pin "33") (pinfunction "IO21_33") (pintype "passive"))
    )
    (net (code "22") (name "/IO22") (class "Default")
      (node (ref "J2") (pin "3") (pinfunction "3_3") (pintype "passive"))
      (node (ref "MD1") (pin "36") (pinfunction "IO22_36") (pintype "passive"))
    )
    (net (code "23") (name "/IO23") (class "Default")
      (node (ref "J2") (pin "4") (pinfunction "4_4") (pintype "passive"))
      (node (ref "MD1") (pin "37") (pinfunction "IO23_37") (pintype "passive"))
    )
    (net (code "24") (name "/IO25") (class "Default")
      (node (ref "J9") (pin "11") (pinfunction "11_11") (pintype "passive"))
      (node (ref "MD1") (pin "10") (pinfunction "IO25_10") (pintype "passive"))
      (node (ref "U6") (pin "3") (pinfunction "IN+_3") (pintype "passive"))
    )
    (net (code "25") (name "/IO26") (class "Default")
      (node (ref "J9") (pin "12") (pinfunction "12_12") (pintype "passive"))
      (node (ref "MD1") (pin "11") (pinfunction "IO26_11") (pintype "passive"))
    )
    (net (code "26") (name "/IO27") (class "Default")
      (node (ref "J9") (pin "13") (pinfunction "13_13") (pintype "passive"))
      (node (ref "MD1") (pin "12") (pinfunction "IO27_12") (pintype "passive"))
    )
    (net (code "27") (name "/IO32") (class "Default")
      (node (ref "J9") (pin "9") (pinfunction "9_9") (pintype "passive"))
      (node (ref "MD1") (pin "8") (pinfunction "IO32_8") (pintype "passive"))
    )
    (net (code "28") (name "/IO33") (class "Default")
      (node (ref "J9") (pin "10") (pinfunction "10_10") (pintype "passive"))
      (node (ref "MD1") (pin "9") (pinfunction "IO33_9") (pintype "passive"))
    )
    (net (code "29") (name "/IO34") (class "Default")
      (node (ref "J9") (pin "7") (pinfunction "7_7") (pintype "passive"))
      (node (ref "MD1") (pin "6") (pinfunction "IO34_6") (pintype "passive"))
    )
    (net (code "30") (name "/IO35") (class "Default")
      (node (ref "J9") (pin "8") (pinfunction "8_8") (pintype "passive"))
      (node (ref "MD1") (pin "7") (pinfunction "IO35_7") (pintype "passive"))
    )
    (net (code "31") (name "/NC") (class "Default")
      (node (ref "J2") (pin "7") (pinfunction "7_7") (pintype "passive"))
      (node (ref "MD1") (pin "32") (pinfunction "NC_32") (pintype "passive"))
    )
    (net (code "32") (name "/RTS") (class "Default")
      (node (ref "Q1") (pin "E") (pinfunction "E_E") (pintype "passive"))
      (node (ref "R20") (pin "1") (pinfunction "1_1") (pintype "passive"))
      (node (ref "R25") (pin "2") (pinfunction "2_2") (pintype "passive"))
      (node (ref "U5") (pin "24") (pinfunction "RTS_24") (pintype "passive"))
    )
    (net (code "33") (name "/RXD") (class "Default")
      (node (ref "R18") (pin "1") (pinfunction "1_1") (pintype "passive"))
      (node (ref "U5") (pin "25") (pinfunction "RXD_25") (pintype "passive"))
    )
    (net (code "34") (name "/RXD0") (class "Default")
      (node (ref "J2") (pin "5") (pinfunction "5_5") (pintype "passive"))
      (node (ref "MD1") (pin "34") (pinfunction "RXD0_34") (pintype "passive"))
      (node (ref "R19") (pin "2") (pinfunction "2_2") (pintype "passive"))
    )
    (net (code "35") (name "/SD0") (class "Default")
      (node (ref "J2") (pin "20") (pinfunction "20_20") (pintype "passive"))
      (node (ref "MD1") (pin "21") (pinfunction "SDO/SD0_21") (pintype "passive"))
    )
    (net (code "36") (name "/SD1") (class "Default")
      (node (ref "J2") (pin "17") (pinfunction "17_17") (pintype "passive"))
      (node (ref "MD1") (pin "22") (pinfunction "SDI/SD1_22") (pintype "passive"))
    )
    (net (code "37") (name "/SD2") (class "Default")
      (node (ref "J9") (pin "18") (pinfunction "18_18") (pintype "passive"))
      (node (ref "MD1") (pin "17") (pinfunction "SHD/SD2_17") (pintype "passive"))
    )
    (net (code "38") (name "/SD3") (class "Default")
      (node (ref "J9") (pin "19") (pinfunction "19_19") (pintype "passive"))
      (node (ref "MD1") (pin "18") (pinfunction "SWP/SD3_18") (pintype "passive"))
    )
    (net (code "39") (name "/SENSOR_VN") (class "Default")
      (node (ref "J9") (pin "6") (pinfunction "6_6") (pintype "passive"))
      (node (ref "MD1") (pin "5") (pinfunction "SENSOR_VN_5") (pintype "passive"))
    )
    (net (code "40") (name "/SENSOR_VP") (class "Default")
      (node (ref "J9") (pin "5") (pinfunction "5_5") (pintype "passive"))
      (node (ref "MD1") (pin "4") (pinfunction "SENSOR_VP_4") (pintype "passive"))
    )
    (net (code "41") (name "/TXD") (class "Default")
      (node (ref "R19") (pin "1") (pinfunction "1_1") (pintype "passive"))
      (node (ref "U5") (pin "26") (pinfunction "TXD_26") (pintype "passive"))
    )
    (net (code "42") (name "/TXD0") (class "Default")
      (node (ref "J2") (pin "6") (pinfunction "6_6") (pintype "passive"))
      (node (ref "MD1") (pin "35") (pinfunction "TXD0_35") (pintype "passive"))
      (node (ref "R18") (pin "2") (pinfunction "2_2") (pintype "passive"))
    )
    (net (code "43") (name "/USB_DN") (class "Default")
      (node (ref "D4") (pin "K") (pinfunction "K_K") (pintype "passive"))
      (node (ref "U5") (pin "5") (pinfunction "D-_5") (pintype "passive"))
      (node (ref "USB") (pin "2") (pinfunction "D-_2") (pintype "passive"))
    )
    (net (code "44") (name "/USB_DP") (class "Default")
      (node (ref "D5") (pin "K") (pinfunction "K_K") (pintype "passive"))
      (node (ref "U5") (pin "4") (pinfunction "D+_4") (pintype "passive"))
      (node (ref "USB") (pin "3") (pinfunction "D+_3") (pintype "passive"))
    )
    (net (code "45") (name "GND") (class "Default")
      (node (ref "C10") (pin "2") (pinfunction "2_2") (pintype "passive"))
      (node (ref "C11") (pin "2") (pinfunction "2_2") (pintype "passive"))
      (node (ref "C12") (pin "2") (pinfunction "2_2") (pintype "passive"))
      (node (ref "C13") (pin "2") (pinfunction "2_2") (pintype "passive"))
      (node (ref "C21") (pin "2") (pinfunction "2_2") (pintype "passive"))
      (node (ref "C22") (pin "2") (pinfunction "2_2") (pintype "passive"))
      (node (ref "C24") (pin "2") (pinfunction "2_2") (pintype "passive"))
      (node (ref "C25") (pin "1") (pinfunction "1_1") (pintype "passive"))
      (node (ref "C26") (pin "1") (pinfunction "1_1") (pintype "passive"))
      (node (ref "C28") (pin "1") (pinfunction "1_1") (pintype "passive"))
      (node (ref "C29") (pin "1") (pinfunction "1_1") (pintype "passive"))
      (node (ref "C3") (pin "2") (pinfunction "2_2") (pintype "passive"))
      (node (ref "C30") (pin "1") (pinfunction "1_1") (pintype "passive"))
      (node (ref "C4") (pin "2") (pinfunction "2_2") (pintype "passive"))
      (node (ref "C7") (pin "2") (pinfunction "2_2") (pintype "passive"))
      (node (ref "C8") (pin "2") (pinfunction "2_2") (pintype "passive"))
      (node (ref "C9") (pin "2") (pinfunction "2_2") (pintype "passive"))
      (node (ref "D4") (pin "A") (pinfunction "A_A") (pintype "passive"))
      (node (ref "D5") (pin "A") (pinfunction "A_A") (pintype "passive"))
      (node (ref "D6") (pin "A") (pinfunction "A_A") (pintype "passive"))
      (node (ref "DS1") (pin "K") (pinfunction "K_K") (pintype "passive"))
      (node (ref "J10") (pin "2") (pinfunction "2_2") (pintype "passive"))
      (node (ref "J2") (pin "1") (pinfunction "1_1") (pintype "passive"))
      (node (ref "J2") (pin "2") (pinfunction "2_2") (pintype "passive"))
      (node (ref "J3") (pin "2") (pinfunction "2_2") (pintype "passive"))
      (node (ref "J4") (pin "2") (pinfunction "2_2") (pintype "passive"))
      (node (ref "J5") (pin "2") (pinfunction "2_2") (pintype "passive"))
      (node (ref "J6") (pin "2") (pinfunction "2_2") (pintype "passive"))
      (node (ref "J7") (pin "2") (pinfunction "2_2") (pintype "passive"))
      (node (ref "J8") (pin "2") (pinfunction "2_2") (pintype "passive"))
      (node (ref "J9") (pin "1") (pinfunction "1_1") (pintype "passive"))
      (node (ref "J9") (pin "16") (pinfunction "16_16") (pintype "passive"))
      (node (ref "J9") (pin "2") (pinfunction "2_2") (pintype "passive"))
      (node (ref "MD1") (pin "1") (pinfunction "GND_1") (pintype "passive"))
      (node (ref "MD1") (pin "15") (pinfunction "GND_15") (pintype "passive"))
      (node (ref "MD1") (pin "38") (pinfunction "GND_38") (pintype "passive"))
      (node (ref "MD1") (pin "39") (pinfunction "GND_39") (pintype "passive"))
      (node (ref "P1") (pin "4") (pinfunction "4_4") (pintype "passive"))
      (node (ref "R10") (pin "1") (pinfunction "1_1") (pintype "passive"))
      (node (ref "R11") (pin "1") (pinfunction "1_1") (pintype "passive"))
      (node (ref "R13") (pin "1") (pinfunction "1_1") (pintype "passive"))
      (node (ref "R17") (pin "1") (pinfunction "1_1") (pintype "passive"))
      (node (ref "R23") (pin "2") (pinfunction "2_2") (pintype "passive"))
      (node (ref "R4") (pin "1") (pinfunction "1_1") (pintype "passive"))
      (node (ref "R5") (pin "2") (pinfunction "2_2") (pintype "passive"))
      (node (ref "R6") (pin "1") (pinfunction "1_1") (pintype "passive"))
      (node (ref "U1") (pin "1") (pinfunction "PGND_1") (pintype "power_in"))
      (node (ref "U1") (pin "11") (pinfunction "EN2_11") (pintype "input"))
      (node (ref "U1") (pin "20") (pinfunction "PGND_20") (pintype "power_in"))
      (node (ref "U1") (pin "21") (pinfunction "PAD_21") (pintype "passive"))
      (node (ref "U1") (pin "9") (pinfunction "AD_9") (pintype "input"))
      (node (ref "U2") (pin "1") (pinfunction "GND_1") (pintype "power_in"))
      (node (ref "U2") (pin "9") (pinfunction "PAD_9") (pintype "power_in"))
      (node (ref "U3") (pin "1") (pinfunction "GND_1") (pintype "passive"))
      (node (ref "U4") (pin "6") (pinfunction "INH_6") (pintype "input"))
      (node (ref "U4") (pin "7") (pinfunction "VEE_7") (pintype "power_in"))
      (node (ref "U4") (pin "8") (pinfunction "VSS_8") (pintype "power_in"))
      (node (ref "U5") (pin "29") (pinfunction "EP_29") (pintype "passive"))
      (node (ref "U5") (pin "3") (pinfunction "GND_3") (pintype "passive"))
      (node (ref "U6") (pin "2") (pinfunction "IN-_2") (pintype "passive"))
      (node (ref "U6") (pin "4") (pinfunction "GND_4") (pintype "passive"))
      (node (ref "USB") (pin "5") (pinfunction "-_5") (pintype "passive"))
    )
    (net (code "46") (name "Net-(C14-Pad2)") (class "Default")
      (node (ref "C14") (pin "2") (pinfunction "2_2") (pintype "passive"))
      (node (ref "C15") (pin "2") (pinfunction "2_2") (pintype "passive"))
      (node (ref "C18") (pin "2") (pinfunction "2_2") (pintype "passive"))
      (node (ref "J1") (pin "1") (pinfunction "1_1") (pintype "passive"))
    )
    (net (code "47") (name "Net-(D1-PadA)") (class "Default")
      (node (ref "D1") (pin "A") (pinfunction "A_A") (pintype "passive"))
      (node (ref "R7") (pin "1") (pinfunction "1_1") (pintype "passive"))
    )
    (net (code "48") (name "Net-(DS1-PadA)") (class "Default")
      (node (ref "DS1") (pin "A") (pinfunction "A_A") (pintype "passive"))
      (node (ref "R15") (pin "1") (pinfunction "1_1") (pintype "passive"))
    )
    (net (code "49") (name "Net-(J6-Pad1)") (class "Default")
      (node (ref "J6") (pin "1") (pinfunction "1_1") (pintype "passive"))
      (node (ref "U4") (pin "5") (pinfunction "5_5") (pintype "passive"))
    )
    (net (code "50") (name "Net-(J10-Pad1)") (class "Default")
      (node (ref "J10") (pin "1") (pinfunction "1_1") (pintype "passive"))
      (node (ref "R8") (pin "2") (pinfunction "2_2") (pintype "passive"))
    )
    (net (code "51") (name "Net-(Q1-PadB)") (class "Default")
      (node (ref "Q1") (pin "B") (pinfunction "B_B") (pintype "passive"))
      (node (ref "R24") (pin "1") (pinfunction "1_1") (pintype "passive"))
    )
    (net (code "52") (name "Net-(Q2-PadB)") (class "Default")
      (node (ref "Q2") (pin "B") (pinfunction "B_B") (pintype "passive"))
      (node (ref "R25") (pin "1") (pinfunction "1_1") (pintype "passive"))
    )
    (net (code "53") (name "Net-(U1-AC1)") (class "Default")
      (node (ref "C1") (pin "2") (pinfunction "2_2") (pintype "passive"))
      (node (ref "C14") (pin "1") (pinfunction "1_1") (pintype "passive"))
      (node (ref "C15") (pin "1") (pinfunction "1_1") (pintype "passive"))
      (node (ref "C16") (pin "1") (pinfunction "1_1") (pintype "passive"))
      (node (ref "C17") (pin "2") (pinfunction "2_2") (pintype "passive"))
      (node (ref "C18") (pin "1") (pinfunction "1_1") (pintype "passive"))
      (node (ref "C2") (pin "2") (pinfunction "2_2") (pintype "passive"))
      (node (ref "C5") (pin "2") (pinfunction "2_2") (pintype "passive"))
      (node (ref "U1") (pin "2") (pinfunction "AC1_2") (pintype "power_in"))
    )
    (net (code "54") (name "Net-(U1-AC2)") (class "Default")
      (node (ref "C16") (pin "2") (pinfunction "2_2") (pintype "passive"))
      (node (ref "C17") (pin "1") (pinfunction "1_1") (pintype "passive"))
      (node (ref "C19") (pin "2") (pinfunction "2_2") (pintype "passive"))
      (node (ref "C20") (pin "2") (pinfunction "2_2") (pintype "passive"))
      (node (ref "C23") (pin "2") (pinfunction "2_2") (pintype "passive"))
      (node (ref "J1") (pin "2") (pinfunction "2_2") (pintype "passive"))
      (node (ref "U1") (pin "19") (pinfunction "AC2_19") (pintype "power_in"))
    )
    (net (code "55") (name "Net-(U1-BAT)") (class "Default")
      (node (ref "C3") (pin "1") (pinfunction "1_1") (pintype "passive"))
      (node (ref "C4") (pin "1") (pinfunction "1_1") (pintype "passive"))
      (node (ref "R1") (pin "1") (pinfunction "1_1") (pintype "passive"))
      (node (ref "U1") (pin "4") (pinfunction "BAT_4") (pintype "power_in"))
    )
    (net (code "56") (name "Net-(U1-BOOT1)") (class "Default")
      (node (ref "C5") (pin "1") (pinfunction "1_1") (pintype "passive"))
      (node (ref "U1") (pin "3") (pinfunction "BOOT1_3") (pintype "power_in"))
    )
    (net (code "57") (name "Net-(U1-BOOT2)") (class "Default")
      (node (ref "C23") (pin "1") (pinfunction "1_1") (pintype "passive"))
      (node (ref "U1") (pin "17") (pinfunction "BOOT2_17") (pintype "power_in"))
    )
    (net (code "58") (name "Net-(U1-CHG)") (class "Default")
      (node (ref "D1") (pin "K") (pinfunction "K_K") (pintype "passive"))
      (node (ref "U1") (pin "7") (pinfunction "CHG_7") (pintype "output"))
    )
    (net (code "59") (name "Net-(U1-CLMP1)") (class "Default")
      (node (ref "C2") (pin "1") (pinfunction "1_1") (pintype "passive"))
      (node (ref "U1") (pin "5") (pinfunction "CLMP1_5") (pintype "output"))
    )
    (net (code "60") (name "Net-(U1-CLMP2)") (class "Default")
      (node (ref "C20") (pin "1") (pinfunction "1_1") (pintype "passive"))
      (node (ref "U1") (pin "16") (pinfunction "CLMP2_16") (pintype "output"))
    )
    (net (code "61") (name "Net-(U1-COMM1)") (class "Default")
      (node (ref "C1") (pin "1") (pinfunction "1_1") (pintype "passive"))
      (node (ref "U1") (pin "6") (pinfunction "COMM1_6") (pintype "output"))
    )
    (net (code "62") (name "Net-(U1-COMM2)") (class "Default")
      (node (ref "C19") (pin "1") (pinfunction "1_1") (pintype "passive"))
      (node (ref "U1") (pin "15") (pinfunction "COMM2_15") (pintype "output"))
    )
    (net (code "63") (name "Net-(U1-FOD)") (class "Default")
      (node (ref "R12") (pin "1") (pinfunction "1_1") (pintype "passive"))
      (node (ref "R13") (pin "2") (pinfunction "2_2") (pintype "passive"))
      (node (ref "R9") (pin "1") (pinfunction "1_1") (pintype "passive"))
      (node (ref "U1") (pin "14") (pinfunction "FOD_14") (pintype "passive"))
    )
    (net (code "64") (name "Net-(U1-ILIM)") (class "Default")
      (node (ref "R12") (pin "2") (pinfunction "2_2") (pintype "passive"))
      (node (ref "U1") (pin "12") (pinfunction "ILIM_12") (pintype "bidirectional"))
    )
    (net (code "65") (name "Net-(U1-RECT)") (class "Default")
      (node (ref "C10") (pin "1") (pinfunction "1_1") (pintype "passive"))
      (node (ref "C11") (pin "1") (pinfunction "1_1") (pintype "passive"))
      (node (ref "R7") (pin "2") (pinfunction "2_2") (pintype "passive"))
      (node (ref "R9") (pin "2") (pinfunction "2_2") (pintype "passive"))
      (node (ref "U1") (pin "18") (pinfunction "RECT_18") (pintype "power_in"))
    )
    (net (code "66") (name "Net-(U1-TERM)") (class "Default")
      (node (ref "R10") (pin "2") (pinfunction "2_2") (pintype "passive"))
      (node (ref "U1") (pin "10") (pinfunction "TERM_10") (pintype "passive"))
    )
    (net (code "67") (name "Net-(U1-TS{slash}CTRL)") (class "Default")
      (node (ref "R11") (pin "2") (pinfunction "2_2") (pintype "passive"))
      (node (ref "U1") (pin "13") (pinfunction "TS/CTRL_13") (pintype "passive"))
    )
    (net (code "68") (name "Net-(U2-EN)") (class "Default")
      (node (ref "C12") (pin "1") (pinfunction "1_1") (pintype "passive"))
      (node (ref "C13") (pin "1") (pinfunction "1_1") (pintype "passive"))
      (node (ref "L1") (pin "1") (pinfunction "1_1") (pintype "passive"))
      (node (ref "R1") (pin "2") (pinfunction "2_2") (pintype "passive"))
      (node (ref "R4") (pin "2") (pinfunction "2_2") (pintype "passive"))
      (node (ref "U2") (pin "6") (pinfunction "EN_6") (pintype "input"))
      (node (ref "U2") (pin "8") (pinfunction "VIN_8") (pintype "power_in"))
    )
    (net (code "69") (name "Net-(U2-FB)") (class "Default")
      (node (ref "C6") (pin "2") (pinfunction "2_2") (pintype "passive"))
      (node (ref "R2") (pin "1") (pinfunction "1_1") (pintype "passive"))
      (node (ref "R6") (pin "2") (pinfunction "2_2") (pintype "passive"))
      (node (ref "U2") (pin "3") (pinfunction "FB_3") (pintype "passive"))
    )
    (net (code "70") (name "Net-(U2-ILIM)") (class "Default")
      (node (ref "R5") (pin "1") (pinfunction "1_1") (pintype "passive"))
      (node (ref "U2") (pin "4") (pinfunction "ILIM_4") (pintype "passive"))
    )
    (net (code "71") (name "Net-(U2-PG)") (class "Default")
      (node (ref "R3") (pin "1") (pinfunction "1_1") (pintype "passive"))
      (node (ref "R8") (pin "1") (pinfunction "1_1") (pintype "passive"))
      (node (ref "U2") (pin "5") (pinfunction "PG_5") (pintype "output"))
    )
    (net (code "72") (name "Net-(U2-SW)") (class "Default")
      (node (ref "L1") (pin "2") (pinfunction "2_2") (pintype "passive"))
      (node (ref "U2") (pin "7") (pinfunction "SW_7") (pintype "power_in"))
    )
    (net (code "73") (name "Net-(U3-Vin)") (class "Default")
      (node (ref "C26") (pin "2") (pinfunction "2_2") (pintype "passive"))
      (node (ref "D2") (pin "K") (pinfunction "K_K") (pintype "passive"))
      (node (ref "D3") (pin "K") (pinfunction "K_K") (pintype "passive"))
      (node (ref "R15") (pin "2") (pinfunction "2_2") (pintype "passive"))
      (node (ref "U3") (pin "3") (pinfunction "Vin_3") (pintype "passive"))
    )
    (net (code "74") (name "Net-(U4-0)") (class "Default")
      (node (ref "J5") (pin "1") (pinfunction "1_1") (pintype "passive"))
      (node (ref "U4") (pin "13") (pinfunction "0_13") (pintype "passive"))
    )
    (net (code "75") (name "Net-(U4-1)") (class "Default")
      (node (ref "J4") (pin "1") (pinfunction "1_1") (pintype "passive"))
      (node (ref "U4") (pin "14") (pinfunction "1_14") (pintype "passive"))
    )
    (net (code "76") (name "Net-(U4-2)") (class "Default")
      (node (ref "J3") (pin "1") (pinfunction "1_1") (pintype "passive"))
      (node (ref "U4") (pin "15") (pinfunction "2_15") (pintype "passive"))
    )
    (net (code "77") (name "Net-(U4-3)") (class "Default")
      (node (ref "J7") (pin "1") (pinfunction "1_1") (pintype "passive"))
      (node (ref "U4") (pin "12") (pinfunction "3_12") (pintype "passive"))
    )
    (net (code "78") (name "Net-(U4-4)") (class "Default")
      (node (ref "J8") (pin "1") (pinfunction "1_1") (pintype "passive"))
      (node (ref "U4") (pin "1") (pinfunction "4_1") (pintype "passive"))
    )
    (net (code "79") (name "Net-(U5-RST#)") (class "Default")
      (node (ref "R22") (pin "1") (pinfunction "1_1") (pintype "passive"))
      (node (ref "U5") (pin "9") (pinfunction "RST#_9") (pintype "passive"))
    )
    (net (code "80") (name "Net-(U5-SUSPEND#)") (class "Default")
      (node (ref "R23") (pin "1") (pinfunction "1_1") (pintype "passive"))
      (node (ref "U5") (pin "11") (pinfunction "SUSPEND#_11") (pintype "passive"))
    )
    (net (code "81") (name "Net-(U5-VBUS)") (class "Default")
      (node (ref "R16") (pin "1") (pinfunction "1_1") (pintype "passive"))
      (node (ref "R17") (pin "2") (pinfunction "2_2") (pintype "passive"))
      (node (ref "U5") (pin "8") (pinfunction "VBUS_8") (pintype "passive"))
    )
    (net (code "82") (name "Net-(U6-VOUT)") (class "Default")
      (node (ref "C27") (pin "1") (pinfunction "1_1") (pintype "passive"))
      (node (ref "C28") (pin "2") (pinfunction "2_2") (pintype "passive"))
      (node (ref "D7") (pin "A") (pinfunction "A_A") (pintype "passive"))
      (node (ref "P1") (pin "1") (pinfunction "1_1") (pintype "passive"))
      (node (ref "U6") (pin "5") (pinfunction "VOUT_5") (pintype "passive"))
    )
    (net (code "83") (name "Net-(USB-+)") (class "Default")
      (node (ref "D3") (pin "A") (pinfunction "A_A") (pintype "passive"))
      (node (ref "D6") (pin "K") (pinfunction "K_K") (pintype "passive"))
      (node (ref "R16") (pin "2") (pinfunction "2_2") (pintype "passive"))
      (node (ref "USB") (pin "1") (pinfunction "+_1") (pintype "passive"))
    )
    (net (code "84") (name "unconnected-(U1-AD-EN-Pad8)") (class "Default")
      (node (ref "U1") (pin "8") (pinfunction "AD-EN_8") (pintype "output"))
    )
    (net (code "85") (name "unconnected-(U4-6-Pad2)") (class "Default")
      (node (ref "U4") (pin "2") (pinfunction "6_2") (pintype "passive"))
    )
    (net (code "86") (name "unconnected-(U4-7-Pad4)") (class "Default")
      (node (ref "U4") (pin "4") (pinfunction "7_4") (pintype "passive"))
    )
    (net (code "87") (name "unconnected-(U5-DCD-Pad1)") (class "Default")
      (node (ref "U5") (pin "1") (pinfunction "DCD_1") (pintype "passive"))
    )
    (net (code "88") (name "unconnected-(U5-DSR-Pad27)") (class "Default")
      (node (ref "U5") (pin "27") (pinfunction "DSR_27") (pintype "passive"))
    )
    (net (code "89") (name "unconnected-(U5-NC-Pad10)") (class "Default")
      (node (ref "U5") (pin "10") (pinfunction "NC_10") (pintype "passive"))
    )
    (net (code "90") (name "unconnected-(U5-NC-Pad13)") (class "Default")
      (node (ref "U5") (pin "13") (pinfunction "NC_13") (pintype "passive"))
    )
    (net (code "91") (name "unconnected-(U5-NC-Pad14)") (class "Default")
      (node (ref "U5") (pin "14") (pinfunction "NC_14") (pintype "passive"))
    )
    (net (code "92") (name "unconnected-(U5-NC-Pad15)") (class "Default")
      (node (ref "U5") (pin "15") (pinfunction "NC_15") (pintype "passive"))
    )
    (net (code "93") (name "unconnected-(U5-NC-Pad16)") (class "Default")
      (node (ref "U5") (pin "16") (pinfunction "NC_16") (pintype "passive"))
    )
    (net (code "94") (name "unconnected-(U5-NC-Pad17)") (class "Default")
      (node (ref "U5") (pin "17") (pinfunction "NC_17") (pintype "passive"))
    )
    (net (code "95") (name "unconnected-(U5-NC-Pad18)") (class "Default")
      (node (ref "U5") (pin "18") (pinfunction "NC_18") (pintype "passive"))
    )
    (net (code "96") (name "unconnected-(U5-NC-Pad19)") (class "Default")
      (node (ref "U5") (pin "19") (pinfunction "NC_19") (pintype "passive"))
    )
    (net (code "97") (name "unconnected-(U5-NC-Pad20)") (class "Default")
      (node (ref "U5") (pin "20") (pinfunction "NC_20") (pintype "passive"))
    )
    (net (code "98") (name "unconnected-(U5-NC-Pad21)") (class "Default")
      (node (ref "U5") (pin "21") (pinfunction "NC_21") (pintype "passive"))
    )
    (net (code "99") (name "unconnected-(U5-NC-Pad22)") (class "Default")
      (node (ref "U5") (pin "22") (pinfunction "NC_22") (pintype "passive"))
    )
    (net (code "100") (name "unconnected-(U5-RI-Pad2)") (class "Default")
      (node (ref "U5") (pin "2") (pinfunction "RI_2") (pintype "passive"))
    )
    (net (code "101") (name "unconnected-(U5-SUSPEND-Pad12)") (class "Default")
      (node (ref "U5") (pin "12") (pinfunction "SUSPEND_12") (pintype "passive"))
    )
    (net (code "102") (name "unconnected-(U6-BYPASS-Pad7)") (class "Default")
      (node (ref "U6") (pin "7") (pinfunction "BYPASS_7") (pintype "passive"))
    )
    (net (code "103") (name "unconnected-(U6-GAIN-Pad1)") (class "Default")
      (node (ref "U6") (pin "1") (pinfunction "GAIN_1") (pintype "passive"))
    )
    (net (code "104") (name "unconnected-(U6-GAIN-Pad8)") (class "Default")
      (node (ref "U6") (pin "8") (pinfunction "GAIN_8") (pintype "passive"))
    )
    (net (code "105") (name "unconnected-(USB-ID-Pad4)") (class "Default")
      (node (ref "USB") (pin "4") (pinfunction "ID_4") (pintype "passive"))
    )
  )
)
